# GyroAccel.net
KiCad netlist of a schematic drawn in Altium Designer
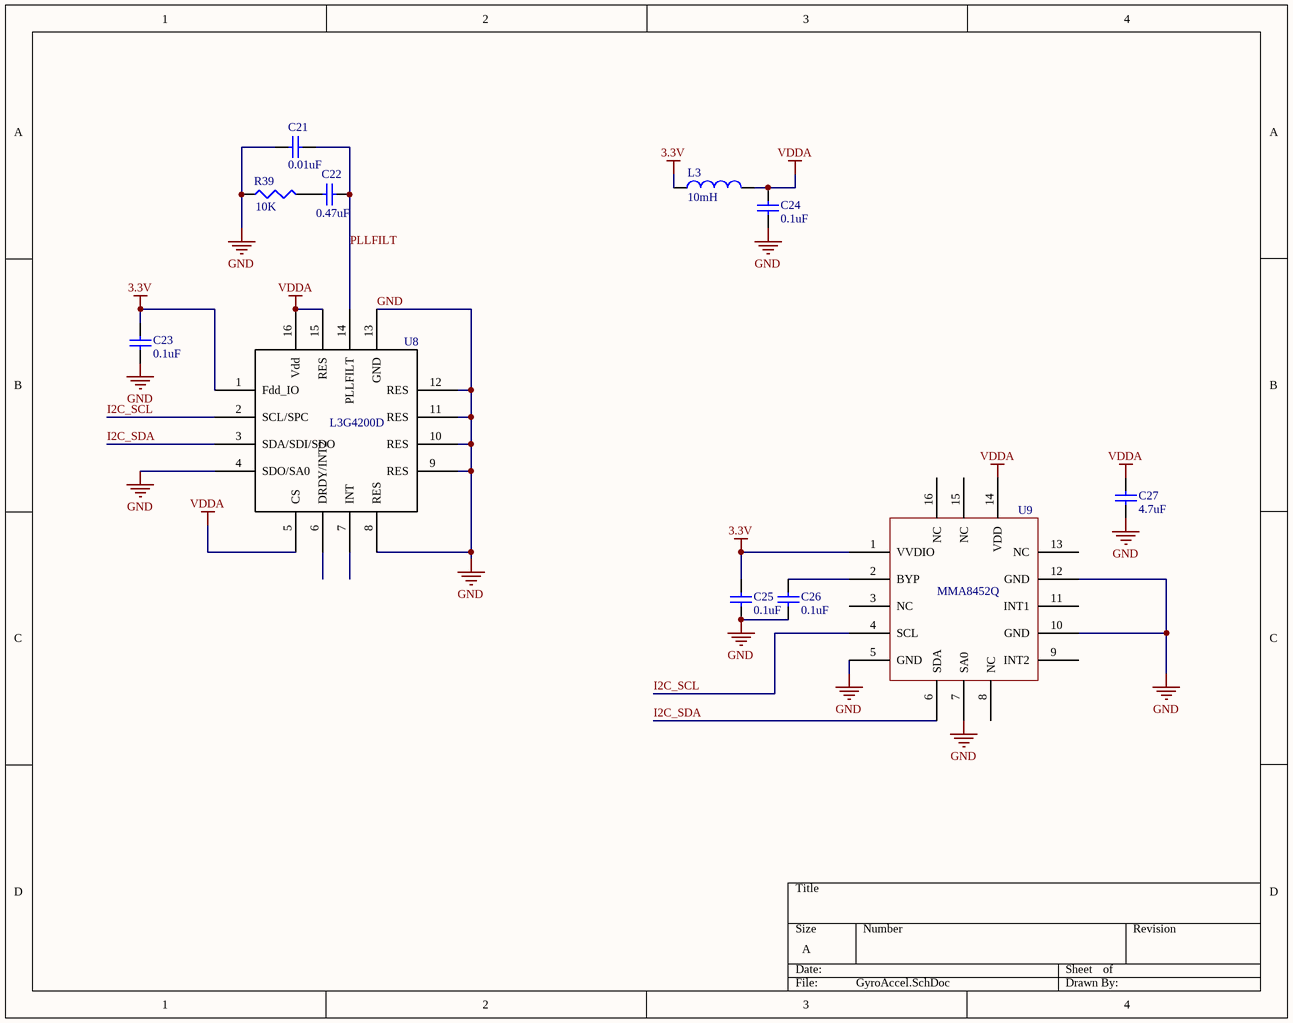
[diagram p0: GyroAccel.SchDoc]

(export (version "E")
  (design (tool "Eeschema 10.0.6"))
  (components
    (comp (ref "C21")
      (value "0.01uF")
      (footprint "CAPC1005L")
      (description "Capacitor (Semiconductor SIM Model)")
      (fields (field (name "Comment") "Cap Semi") (field (name "PUBLISHER") "Altium Limited"))
      (libsource (lib "Miscellaneous Devices") (part "Cap Semi"))
    )
    (comp (ref "C22")
      (value "0.47uF")
      (footprint "CAPC1005L")
      (description "Capacitor (Semiconductor SIM Model)")
      (fields (field (name "Comment") "Cap Semi") (field (name "PUBLISHER") "Altium Limited"))
      (libsource (lib "Miscellaneous Devices") (part "Cap Semi"))
    )
    (comp (ref "C23")
      (value "0.1uF")
      (footprint "CAPC1005L")
      (description "Capacitor (Semiconductor SIM Model)")
      (fields (field (name "Comment") "Cap Semi") (field (name "PUBLISHER") "Altium Limited"))
      (libsource (lib "Miscellaneous Devices") (part "Cap Semi"))
    )
    (comp (ref "C24")
      (value "0.1uF")
      (footprint "CAPC1005L")
      (description "Capacitor (Semiconductor SIM Model)")
      (fields (field (name "Comment") "Cap Semi") (field (name "PUBLISHER") "Altium Limited"))
      (libsource (lib "Miscellaneous Devices") (part "Cap Semi"))
    )
    (comp (ref "C25")
      (value "0.1uF")
      (footprint "CAPC1005L")
      (description "Capacitor (Semiconductor SIM Model)")
      (fields (field (name "Comment") "Cap Semi") (field (name "PUBLISHER") "Altium Limited"))
      (libsource (lib "Miscellaneous Devices") (part "Cap Semi"))
    )
    (comp (ref "C26")
      (value "0.1uF")
      (footprint "CAPC1005L")
      (description "Capacitor (Semiconductor SIM Model)")
      (fields (field (name "Comment") "Cap Semi") (field (name "PUBLISHER") "Altium Limited"))
      (libsource (lib "Miscellaneous Devices") (part "Cap Semi"))
    )
    (comp (ref "C27")
      (value "4.7uF")
      (footprint "CAPC1608L")
      (description "Capacitor (Semiconductor SIM Model)")
      (fields (field (name "Comment") "Cap Semi") (field (name "PUBLISHER") "Altium Limited"))
      (libsource (lib "Miscellaneous Devices") (part "Cap Semi"))
    )
    (comp (ref "L3")
      (value "10mH")
      (footprint "INDC2012L")
      (description "Inductor")
      (fields (field (name "PUBLISHER") "Altium Limited"))
      (libsource (lib "Miscellaneous Devices") (part "Inductor"))
    )
    (comp (ref "R39")
      (value "10K")
      (footprint "RESC1608L")
      (description "Resistor")
      (fields (field (name "Comment") "Res3") (field (name "PUBLISHER") "Altium Limited"))
      (libsource (lib "Miscellaneous Devices") (part "Res3"))
    )
    (comp (ref "U8")
      (value "L3G4200D")
      (footprint "L3G2004D")
      (description "3axis gyroscope, SPI")
      (libsource (lib "mrone") (part "L3G4200D"))
    )
    (comp (ref "U9") (value "MMA8452Q") (footprint "MMA8452Q") (libsource (lib "mrone") (part "MMA8452Q")))
  )
  (nets
    (net (code "1") (name "/I2C_SCL") (class "Default")
      (node (ref "U8") (pin "2") (pinfunction "SCL/SPC_2") (pintype "passive"))
      (node (ref "U9") (pin "4") (pinfunction "SCL_4") (pintype "passive"))
    )
    (net (code "2") (name "/I2C_SDA") (class "Default")
      (node (ref "U8") (pin "3") (pinfunction "SDA/SDI/SDO_3") (pintype "passive"))
      (node (ref "U9") (pin "6") (pinfunction "SDA_6") (pintype "passive"))
    )
    (net (code "3") (name "/PLLFILT") (class "Default")
      (node (ref "C21") (pin "1") (pinfunction "1_1") (pintype "passive"))
      (node (ref "C22") (pin "1") (pinfunction "1_1") (pintype "passive"))
      (node (ref "U8") (pin "14") (pinfunction "PLLFILT_14") (pintype "passive"))
    )
    (net (code "4") (name "3.3V") (class "Default")
      (node (ref "C23") (pin "2") (pinfunction "2_2") (pintype "passive"))
      (node (ref "C25") (pin "2") (pinfunction "2_2") (pintype "passive"))
      (node (ref "L3") (pin "2") (pinfunction "2_2") (pintype "passive"))
      (node (ref "U8") (pin "1") (pinfunction "Fdd_IO_1") (pintype "passive"))
      (node (ref "U9") (pin "1") (pinfunction "VVDIO_1") (pintype "passive"))
    )
    (net (code "5") (name "GND") (class "Default")
      (node (ref "C21") (pin "2") (pinfunction "2_2") (pintype "passive"))
      (node (ref "C23") (pin "1") (pinfunction "1_1") (pintype "passive"))
      (node (ref "C24") (pin "1") (pinfunction "1_1") (pintype "passive"))
      (node (ref "C25") (pin "1") (pinfunction "1_1") (pintype "passive"))
      (node (ref "C26") (pin "1") (pinfunction "1_1") (pintype "passive"))
      (node (ref "C27") (pin "1") (pinfunction "1_1") (pintype "passive"))
      (node (ref "R39") (pin "1") (pinfunction "1_1") (pintype "passive"))
      (node (ref "U8") (pin "10") (pinfunction "RES_10") (pintype "passive"))
      (node (ref "U8") (pin "11") (pinfunction "RES_11") (pintype "passive"))
      (node (ref "U8") (pin "12") (pinfunction "RES_12") (pintype "passive"))
      (node (ref "U8") (pin "13") (pinfunction "GND_13") (pintype "passive"))
      (node (ref "U8") (pin "4") (pinfunction "SDO/SA0_4") (pintype "passive"))
      (node (ref "U8") (pin "8") (pinfunction "RES_8") (pintype "passive"))
      (node (ref "U8") (pin "9") (pinfunction "RES_9") (pintype "passive"))
      (node (ref "U9") (pin "10") (pinfunction "GND_10") (pintype "passive"))
      (node (ref "U9") (pin "12") (pinfunction "GND_12") (pintype "passive"))
      (node (ref "U9") (pin "5") (pinfunction "GND_5") (pintype "passive"))
      (node (ref "U9") (pin "7") (pinfunction "SA0_7") (pintype "passive"))
    )
    (net (code "6") (name "Net-(C22-Pad2)") (class "Default")
      (node (ref "C22") (pin "2") (pinfunction "2_2") (pintype "passive"))
      (node (ref "R39") (pin "2") (pinfunction "2_2") (pintype "passive"))
    )
    (net (code "7") (name "Net-(U9-BYP)") (class "Default")
      (node (ref "C26") (pin "2") (pinfunction "2_2") (pintype "passive"))
      (node (ref "U9") (pin "2") (pinfunction "BYP_2") (pintype "passive"))
    )
    (net (code "8") (name "VDDA") (class "Default")
      (node (ref "C24") (pin "2") (pinfunction "2_2") (pintype "passive"))
      (node (ref "C27") (pin "2") (pinfunction "2_2") (pintype "passive"))
      (node (ref "L3") (pin "1") (pinfunction "1_1") (pintype "passive"))
      (node (ref "U8") (pin "15") (pinfunction "RES_15") (pintype "passive"))
      (node (ref "U8") (pin "16") (pinfunction "Vdd_16") (pintype "passive"))
      (node (ref "U8") (pin "5") (pinfunction "CS_5") (pintype "passive"))
      (node (ref "U9") (pin "14") (pinfunction "VDD_14") (pintype "passive"))
    )
    (net (code "9") (name "unconnected-(U8-DRDY{slash}INT2-Pad6)") (class "Default")
      (node (ref "U8") (pin "6") (pinfunction "DRDY/INT2_6") (pintype "passive"))
    )
    (net (code "10") (name "unconnected-(U8-INT-Pad7)") (class "Default")
      (node (ref "U8") (pin "7") (pinfunction "INT_7") (pintype "passive"))
    )
    (net (code "11") (name "unconnected-(U9-INT1-Pad11)") (class "Default")
      (node (ref "U9") (pin "11") (pinfunction "INT1_11") (pintype "passive"))
    )
    (net (code "12") (name "unconnected-(U9-INT2-Pad9)") (class "Default")
      (node (ref "U9") (pin "9") (pinfunction "INT2_9") (pintype "passive"))
    )
    (net (code "13") (name "unconnected-(U9-NC-Pad3)") (class "Default")
      (node (ref "U9") (pin "3") (pinfunction "NC_3") (pintype "passive"))
    )
    (net (code "14") (name "unconnected-(U9-NC-Pad8)") (class "Default")
      (node (ref "U9") (pin "8") (pinfunction "NC_8") (pintype "passive"))
    )
    (net (code "15") (name "unconnected-(U9-NC-Pad13)") (class "Default")
      (node (ref "U9") (pin "13") (pinfunction "NC_13") (pintype "passive"))
    )
    (net (code "16") (name "unconnected-(U9-NC-Pad15)") (class "Default")
      (node (ref "U9") (pin "15") (pinfunction "NC_15") (pintype "passive"))
    )
    (net (code "17") (name "unconnected-(U9-NC-Pad16)") (class "Default")
      (node (ref "U9") (pin "16") (pinfunction "NC_16") (pintype "passive"))
    )
  )
)
